# PGTN022_euclidean_logic.net
KiCad netlist of a schematic drawn in EAGLE
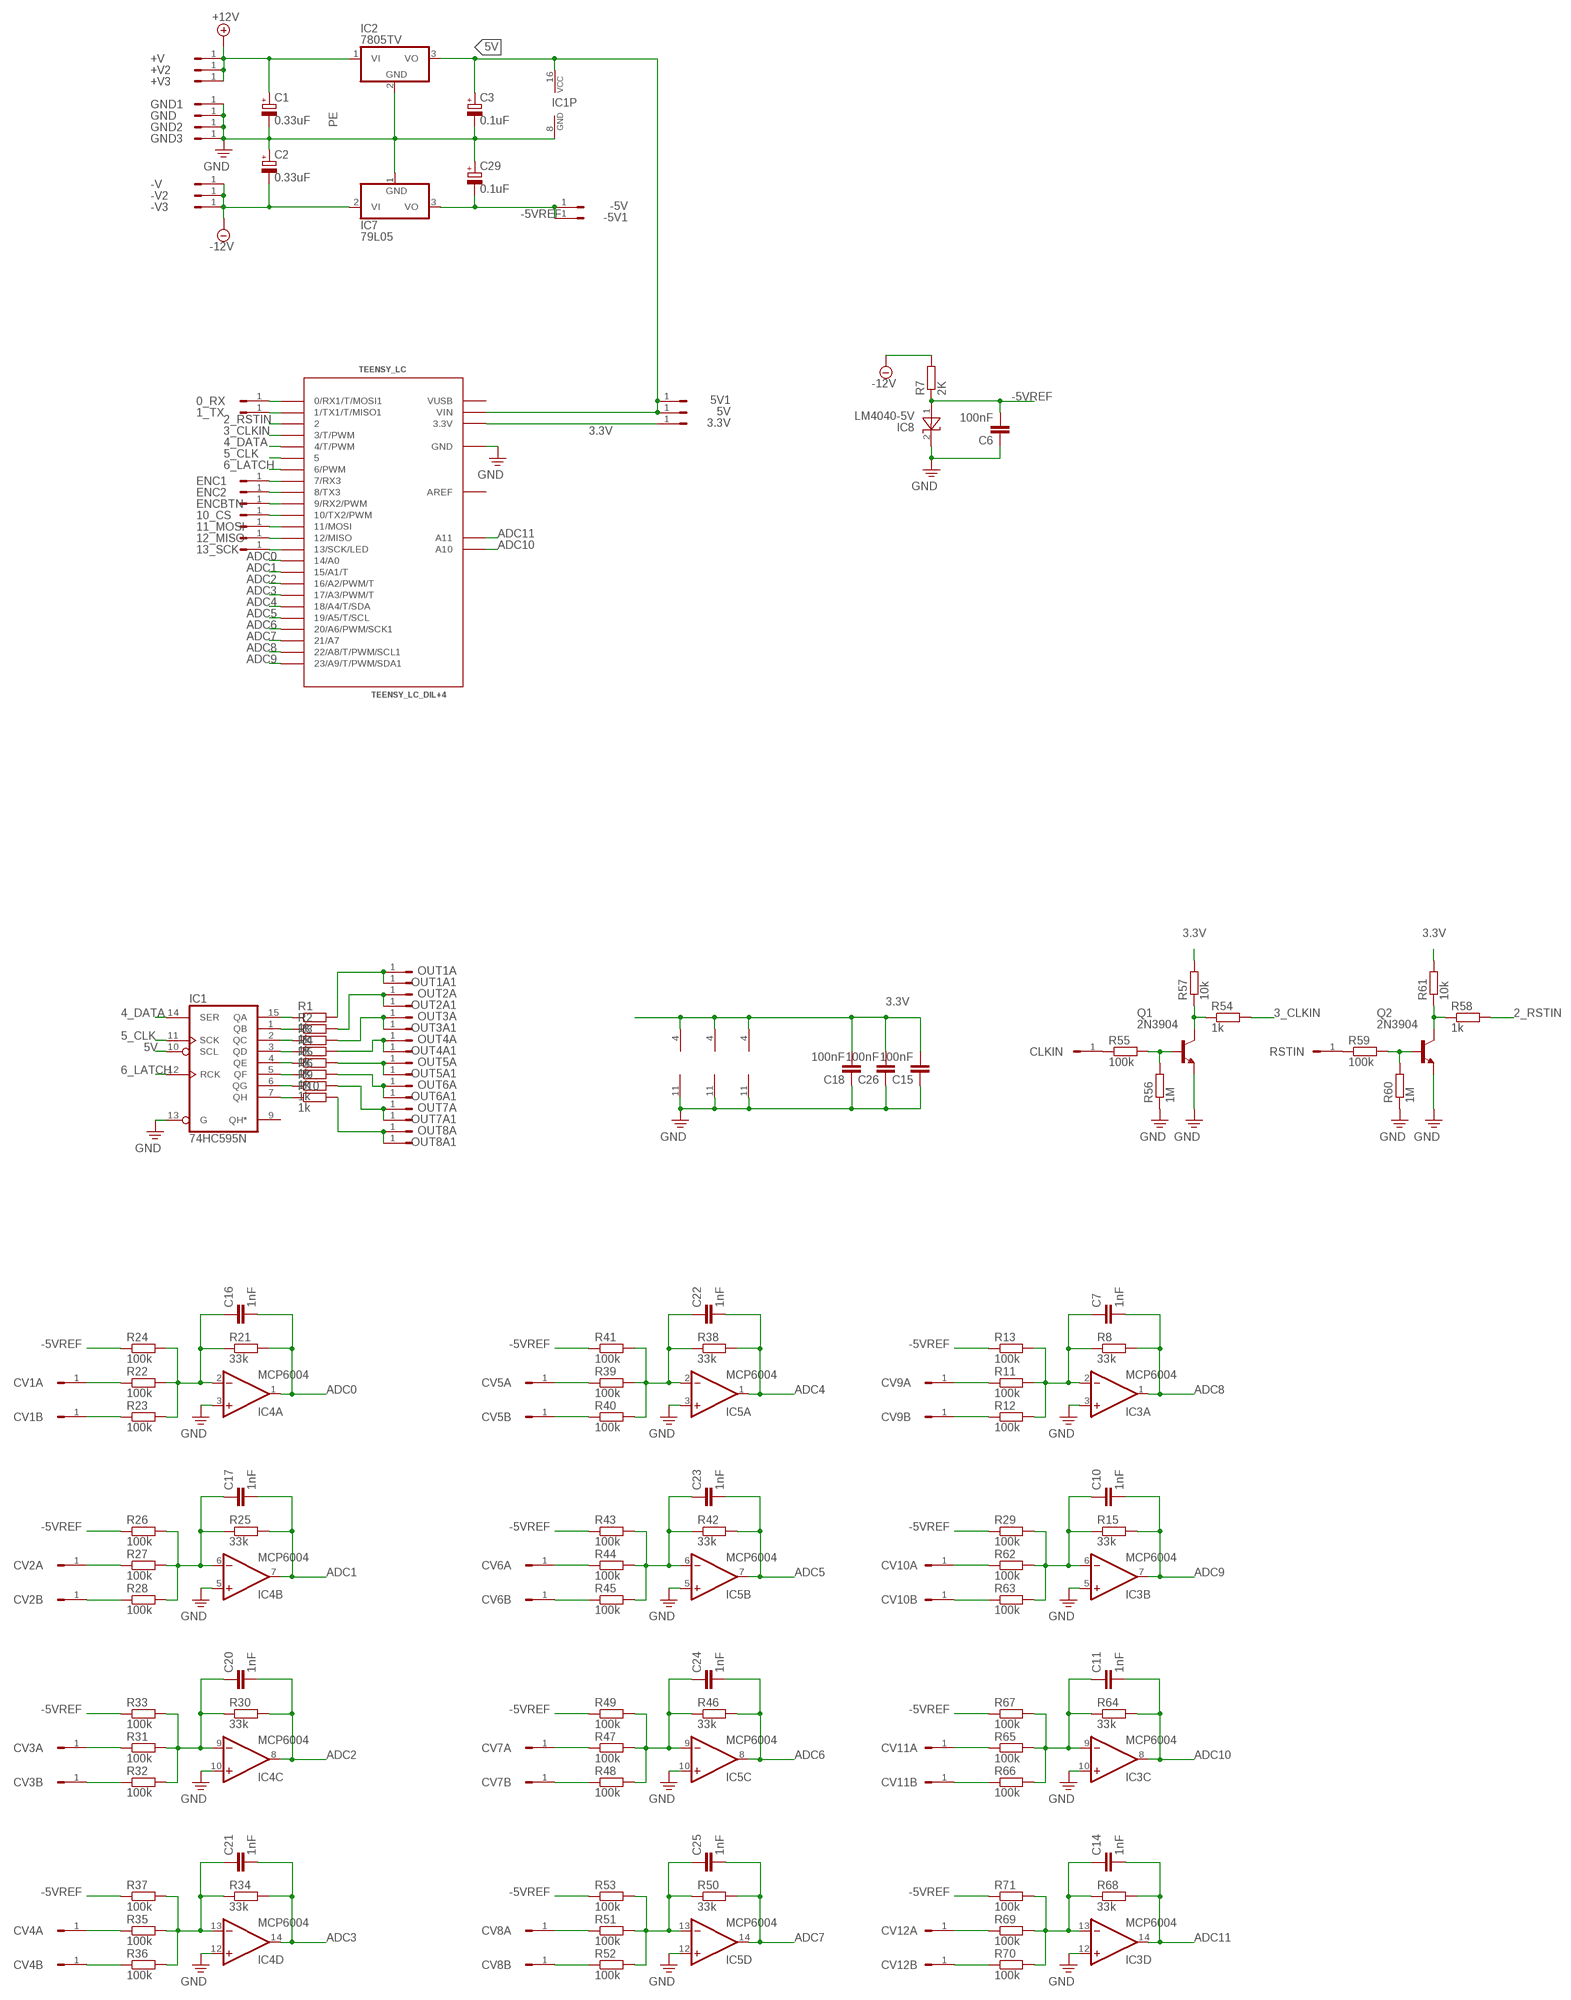
[diagram p0: schematic, sheet 1]

(export (version "E")
  (design (tool "Eeschema 10.0.6"))
  (components
    (comp (ref "+V")
      (value "HEADER/MALE/01")
      (footprint "eagle-import:HEADER_MALE_01")
      (fields (field (name "SPICEPREFIX") "X"))
      (libsource (lib "eagle-import") (part "HEADER/MALE/01"))
    )
    (comp (ref "+V2")
      (value "HEADER/MALE/01")
      (footprint "eagle-import:HEADER_MALE_01")
      (fields (field (name "SPICEPREFIX") "X"))
      (libsource (lib "eagle-import") (part "HEADER/MALE/01"))
    )
    (comp (ref "+V3")
      (value "HEADER/MALE/01")
      (footprint "eagle-import:HEADER_MALE_01")
      (fields (field (name "SPICEPREFIX") "X"))
      (libsource (lib "eagle-import") (part "HEADER/MALE/01"))
    )
    (comp (ref "-5V")
      (value "HEADER/MALE/01")
      (footprint "eagle-import:HEADER_MALE_01")
      (fields (field (name "SPICEPREFIX") "X"))
      (libsource (lib "eagle-import") (part "HEADER/MALE/01"))
    )
    (comp (ref "-5V1")
      (value "HEADER/MALE/01")
      (footprint "eagle-import:HEADER_MALE_01")
      (fields (field (name "SPICEPREFIX") "X"))
      (libsource (lib "eagle-import") (part "HEADER/MALE/01"))
    )
    (comp (ref "-V")
      (value "HEADER/MALE/01")
      (footprint "eagle-import:HEADER_MALE_01")
      (fields (field (name "SPICEPREFIX") "X"))
      (libsource (lib "eagle-import") (part "HEADER/MALE/01"))
    )
    (comp (ref "-V2")
      (value "HEADER/MALE/01")
      (footprint "eagle-import:HEADER_MALE_01")
      (fields (field (name "SPICEPREFIX") "X"))
      (libsource (lib "eagle-import") (part "HEADER/MALE/01"))
    )
    (comp (ref "-V3")
      (value "HEADER/MALE/01")
      (footprint "eagle-import:HEADER_MALE_01")
      (fields (field (name "SPICEPREFIX") "X"))
      (libsource (lib "eagle-import") (part "HEADER/MALE/01"))
    )
    (comp (ref "0_RX")
      (value "HEADER/MALE/01")
      (footprint "eagle-import:HEADER_MALE_01")
      (fields (field (name "SPICEPREFIX") "X"))
      (libsource (lib "eagle-import") (part "HEADER/MALE/01"))
    )
    (comp (ref "1_TX")
      (value "HEADER/MALE/01")
      (footprint "eagle-import:HEADER_MALE_01")
      (fields (field (name "SPICEPREFIX") "X"))
      (libsource (lib "eagle-import") (part "HEADER/MALE/01"))
    )
    (comp (ref "3.3V")
      (value "HEADER/MALE/01")
      (footprint "eagle-import:HEADER_MALE_01")
      (fields (field (name "SPICEPREFIX") "X"))
      (libsource (lib "eagle-import") (part "HEADER/MALE/01"))
    )
    (comp (ref "5V")
      (value "HEADER/MALE/01")
      (footprint "eagle-import:HEADER_MALE_01")
      (fields (field (name "SPICEPREFIX") "X"))
      (libsource (lib "eagle-import") (part "HEADER/MALE/01"))
    )
    (comp (ref "5V1")
      (value "HEADER/MALE/01")
      (footprint "eagle-import:HEADER_MALE_01")
      (fields (field (name "SPICEPREFIX") "X"))
      (libsource (lib "eagle-import") (part "HEADER/MALE/01"))
    )
    (comp (ref "10_CS")
      (value "HEADER/MALE/01")
      (footprint "eagle-import:HEADER_MALE_01")
      (fields (field (name "SPICEPREFIX") "X"))
      (libsource (lib "eagle-import") (part "HEADER/MALE/01"))
    )
    (comp (ref "11_MOSI")
      (value "HEADER/MALE/01")
      (footprint "eagle-import:HEADER_MALE_01")
      (fields (field (name "SPICEPREFIX") "X"))
      (libsource (lib "eagle-import") (part "HEADER/MALE/01"))
    )
    (comp (ref "12_MISO")
      (value "HEADER/MALE/01")
      (footprint "eagle-import:HEADER_MALE_01")
      (fields (field (name "SPICEPREFIX") "X"))
      (libsource (lib "eagle-import") (part "HEADER/MALE/01"))
    )
    (comp (ref "13_SCK")
      (value "HEADER/MALE/01")
      (footprint "eagle-import:HEADER_MALE_01")
      (fields (field (name "SPICEPREFIX") "X"))
      (libsource (lib "eagle-import") (part "HEADER/MALE/01"))
    )
    (comp (ref "C1")
      (value "0.33uF")
      (footprint "eagle-import:E2,5-6")
      (fields (field (name "SPICEPREFIX") "C"))
      (libsource (lib "eagle-import") (part "CAPACITOR/POLARIZEDE2.5-6"))
    )
    (comp (ref "C2")
      (value "0.33uF")
      (footprint "eagle-import:E2,5-6")
      (fields (field (name "SPICEPREFIX") "C"))
      (libsource (lib "eagle-import") (part "CAPACITOR/POLARIZEDE2.5-6"))
    )
    (comp (ref "C3")
      (value "0.1uF")
      (footprint "eagle-import:E2,5-6")
      (fields (field (name "SPICEPREFIX") "C"))
      (libsource (lib "eagle-import") (part "CAPACITOR/POLARIZEDE2.5-6"))
    )
    (comp (ref "C6")
      (value "100nF")
      (footprint "eagle-import:CERAMICDISC_5")
      (libsource (lib "eagle-import") (part "CAPACITORCERAMICDISC/5"))
    )
    (comp (ref "C7")
      (value "1nF")
      (footprint "eagle-import:CERAMICDISC_5")
      (libsource (lib "eagle-import") (part "CAPACITORCERAMICDISC/5"))
    )
    (comp (ref "C10")
      (value "1nF")
      (footprint "eagle-import:CERAMICDISC_5")
      (libsource (lib "eagle-import") (part "CAPACITORCERAMICDISC/5"))
    )
    (comp (ref "C11")
      (value "1nF")
      (footprint "eagle-import:CERAMICDISC_5")
      (libsource (lib "eagle-import") (part "CAPACITORCERAMICDISC/5"))
    )
    (comp (ref "C14")
      (value "1nF")
      (footprint "eagle-import:CERAMICDISC_5")
      (libsource (lib "eagle-import") (part "CAPACITORCERAMICDISC/5"))
    )
    (comp (ref "C15")
      (value "100nF")
      (footprint "eagle-import:CERAMICDISC_5")
      (libsource (lib "eagle-import") (part "CAPACITORCERAMICDISC/5"))
    )
    (comp (ref "C16")
      (value "1nF")
      (footprint "eagle-import:CERAMICDISC_5")
      (libsource (lib "eagle-import") (part "CAPACITORCERAMICDISC/5"))
    )
    (comp (ref "C17")
      (value "1nF")
      (footprint "eagle-import:CERAMICDISC_5")
      (libsource (lib "eagle-import") (part "CAPACITORCERAMICDISC/5"))
    )
    (comp (ref "C18")
      (value "100nF")
      (footprint "eagle-import:CERAMICDISC_5")
      (libsource (lib "eagle-import") (part "CAPACITORCERAMICDISC/5"))
    )
    (comp (ref "C20")
      (value "1nF")
      (footprint "eagle-import:CERAMICDISC_5")
      (libsource (lib "eagle-import") (part "CAPACITORCERAMICDISC/5"))
    )
    (comp (ref "C21")
      (value "1nF")
      (footprint "eagle-import:CERAMICDISC_5")
      (libsource (lib "eagle-import") (part "CAPACITORCERAMICDISC/5"))
    )
    (comp (ref "C22")
      (value "1nF")
      (footprint "eagle-import:CERAMICDISC_5")
      (libsource (lib "eagle-import") (part "CAPACITORCERAMICDISC/5"))
    )
    (comp (ref "C23")
      (value "1nF")
      (footprint "eagle-import:CERAMICDISC_5")
      (libsource (lib "eagle-import") (part "CAPACITORCERAMICDISC/5"))
    )
    (comp (ref "C24")
      (value "1nF")
      (footprint "eagle-import:CERAMICDISC_5")
      (libsource (lib "eagle-import") (part "CAPACITORCERAMICDISC/5"))
    )
    (comp (ref "C25")
      (value "1nF")
      (footprint "eagle-import:CERAMICDISC_5")
      (libsource (lib "eagle-import") (part "CAPACITORCERAMICDISC/5"))
    )
    (comp (ref "C26")
      (value "100nF")
      (footprint "eagle-import:CERAMICDISC_5")
      (libsource (lib "eagle-import") (part "CAPACITORCERAMICDISC/5"))
    )
    (comp (ref "C29")
      (value "0.1uF")
      (footprint "eagle-import:E2,5-6")
      (fields (field (name "SPICEPREFIX") "C"))
      (libsource (lib "eagle-import") (part "CAPACITOR/POLARIZEDE2.5-6"))
    )
    (comp (ref "CLKIN")
      (value "HEADER/MALE/01")
      (footprint "eagle-import:HEADER_MALE_01")
      (fields (field (name "SPICEPREFIX") "X"))
      (libsource (lib "eagle-import") (part "HEADER/MALE/01"))
    )
    (comp (ref "CV1A")
      (value "HEADER/MALE/01")
      (footprint "eagle-import:HEADER_MALE_01")
      (fields (field (name "SPICEPREFIX") "X"))
      (libsource (lib "eagle-import") (part "HEADER/MALE/01"))
    )
    (comp (ref "CV1B")
      (value "HEADER/MALE/01")
      (footprint "eagle-import:HEADER_MALE_01")
      (fields (field (name "SPICEPREFIX") "X"))
      (libsource (lib "eagle-import") (part "HEADER/MALE/01"))
    )
    (comp (ref "CV2A")
      (value "HEADER/MALE/01")
      (footprint "eagle-import:HEADER_MALE_01")
      (fields (field (name "SPICEPREFIX") "X"))
      (libsource (lib "eagle-import") (part "HEADER/MALE/01"))
    )
    (comp (ref "CV2B")
      (value "HEADER/MALE/01")
      (footprint "eagle-import:HEADER_MALE_01")
      (fields (field (name "SPICEPREFIX") "X"))
      (libsource (lib "eagle-import") (part "HEADER/MALE/01"))
    )
    (comp (ref "CV3A")
      (value "HEADER/MALE/01")
      (footprint "eagle-import:HEADER_MALE_01")
      (fields (field (name "SPICEPREFIX") "X"))
      (libsource (lib "eagle-import") (part "HEADER/MALE/01"))
    )
    (comp (ref "CV3B")
      (value "HEADER/MALE/01")
      (footprint "eagle-import:HEADER_MALE_01")
      (fields (field (name "SPICEPREFIX") "X"))
      (libsource (lib "eagle-import") (part "HEADER/MALE/01"))
    )
    (comp (ref "CV4A")
      (value "HEADER/MALE/01")
      (footprint "eagle-import:HEADER_MALE_01")
      (fields (field (name "SPICEPREFIX") "X"))
      (libsource (lib "eagle-import") (part "HEADER/MALE/01"))
    )
    (comp (ref "CV4B")
      (value "HEADER/MALE/01")
      (footprint "eagle-import:HEADER_MALE_01")
      (fields (field (name "SPICEPREFIX") "X"))
      (libsource (lib "eagle-import") (part "HEADER/MALE/01"))
    )
    (comp (ref "CV5A")
      (value "HEADER/MALE/01")
      (footprint "eagle-import:HEADER_MALE_01")
      (fields (field (name "SPICEPREFIX") "X"))
      (libsource (lib "eagle-import") (part "HEADER/MALE/01"))
    )
    (comp (ref "CV5B")
      (value "HEADER/MALE/01")
      (footprint "eagle-import:HEADER_MALE_01")
      (fields (field (name "SPICEPREFIX") "X"))
      (libsource (lib "eagle-import") (part "HEADER/MALE/01"))
    )
    (comp (ref "CV6A")
      (value "HEADER/MALE/01")
      (footprint "eagle-import:HEADER_MALE_01")
      (fields (field (name "SPICEPREFIX") "X"))
      (libsource (lib "eagle-import") (part "HEADER/MALE/01"))
    )
    (comp (ref "CV6B")
      (value "HEADER/MALE/01")
      (footprint "eagle-import:HEADER_MALE_01")
      (fields (field (name "SPICEPREFIX") "X"))
      (libsource (lib "eagle-import") (part "HEADER/MALE/01"))
    )
    (comp (ref "CV7A")
      (value "HEADER/MALE/01")
      (footprint "eagle-import:HEADER_MALE_01")
      (fields (field (name "SPICEPREFIX") "X"))
      (libsource (lib "eagle-import") (part "HEADER/MALE/01"))
    )
    (comp (ref "CV7B")
      (value "HEADER/MALE/01")
      (footprint "eagle-import:HEADER_MALE_01")
      (fields (field (name "SPICEPREFIX") "X"))
      (libsource (lib "eagle-import") (part "HEADER/MALE/01"))
    )
    (comp (ref "CV8A")
      (value "HEADER/MALE/01")
      (footprint "eagle-import:HEADER_MALE_01")
      (fields (field (name "SPICEPREFIX") "X"))
      (libsource (lib "eagle-import") (part "HEADER/MALE/01"))
    )
    (comp (ref "CV8B")
      (value "HEADER/MALE/01")
      (footprint "eagle-import:HEADER_MALE_01")
      (fields (field (name "SPICEPREFIX") "X"))
      (libsource (lib "eagle-import") (part "HEADER/MALE/01"))
    )
    (comp (ref "CV9A")
      (value "HEADER/MALE/01")
      (footprint "eagle-import:HEADER_MALE_01")
      (fields (field (name "SPICEPREFIX") "X"))
      (libsource (lib "eagle-import") (part "HEADER/MALE/01"))
    )
    (comp (ref "CV9B")
      (value "HEADER/MALE/01")
      (footprint "eagle-import:HEADER_MALE_01")
      (fields (field (name "SPICEPREFIX") "X"))
      (libsource (lib "eagle-import") (part "HEADER/MALE/01"))
    )
    (comp (ref "CV10A")
      (value "HEADER/MALE/01")
      (footprint "eagle-import:HEADER_MALE_01")
      (fields (field (name "SPICEPREFIX") "X"))
      (libsource (lib "eagle-import") (part "HEADER/MALE/01"))
    )
    (comp (ref "CV10B")
      (value "HEADER/MALE/01")
      (footprint "eagle-import:HEADER_MALE_01")
      (fields (field (name "SPICEPREFIX") "X"))
      (libsource (lib "eagle-import") (part "HEADER/MALE/01"))
    )
    (comp (ref "CV11A")
      (value "HEADER/MALE/01")
      (footprint "eagle-import:HEADER_MALE_01")
      (fields (field (name "SPICEPREFIX") "X"))
      (libsource (lib "eagle-import") (part "HEADER/MALE/01"))
    )
    (comp (ref "CV11B")
      (value "HEADER/MALE/01")
      (footprint "eagle-import:HEADER_MALE_01")
      (fields (field (name "SPICEPREFIX") "X"))
      (libsource (lib "eagle-import") (part "HEADER/MALE/01"))
    )
    (comp (ref "CV12A")
      (value "HEADER/MALE/01")
      (footprint "eagle-import:HEADER_MALE_01")
      (fields (field (name "SPICEPREFIX") "X"))
      (libsource (lib "eagle-import") (part "HEADER/MALE/01"))
    )
    (comp (ref "CV12B")
      (value "HEADER/MALE/01")
      (footprint "eagle-import:HEADER_MALE_01")
      (fields (field (name "SPICEPREFIX") "X"))
      (libsource (lib "eagle-import") (part "HEADER/MALE/01"))
    )
    (comp (ref "ENC1")
      (value "HEADER/MALE/01")
      (footprint "eagle-import:HEADER_MALE_01")
      (fields (field (name "SPICEPREFIX") "X"))
      (libsource (lib "eagle-import") (part "HEADER/MALE/01"))
    )
    (comp (ref "ENC2")
      (value "HEADER/MALE/01")
      (footprint "eagle-import:HEADER_MALE_01")
      (fields (field (name "SPICEPREFIX") "X"))
      (libsource (lib "eagle-import") (part "HEADER/MALE/01"))
    )
    (comp (ref "ENCBTN")
      (value "HEADER/MALE/01")
      (footprint "eagle-import:HEADER_MALE_01")
      (fields (field (name "SPICEPREFIX") "X"))
      (libsource (lib "eagle-import") (part "HEADER/MALE/01"))
    )
    (comp (ref "GND")
      (value "HEADER/MALE/01")
      (footprint "eagle-import:HEADER_MALE_01")
      (fields (field (name "SPICEPREFIX") "X"))
      (libsource (lib "eagle-import") (part "HEADER/MALE/01"))
    )
    (comp (ref "GND1")
      (value "HEADER/MALE/01")
      (footprint "eagle-import:HEADER_MALE_01")
      (fields (field (name "SPICEPREFIX") "X"))
      (libsource (lib "eagle-import") (part "HEADER/MALE/01"))
    )
    (comp (ref "GND2")
      (value "HEADER/MALE/01")
      (footprint "eagle-import:HEADER_MALE_01")
      (fields (field (name "SPICEPREFIX") "X"))
      (libsource (lib "eagle-import") (part "HEADER/MALE/01"))
    )
    (comp (ref "GND3")
      (value "HEADER/MALE/01")
      (footprint "eagle-import:HEADER_MALE_01")
      (fields (field (name "SPICEPREFIX") "X"))
      (libsource (lib "eagle-import") (part "HEADER/MALE/01"))
    )
    (comp (ref "IC1")
      (value "74HC595N")
      (footprint "eagle-import:DIL16")
      (libsource (lib "eagle-import") (part "74595NHC"))
    )
    (comp (ref "IC2")
      (value "7805TV")
      (footprint "eagle-import:TO220V")
      (libsource (lib "eagle-import") (part "78TV05"))
    )
    (comp (ref "IC3")
      (value "MCP6004")
      (footprint "eagle-import:DIL14")
      (libsource (lib "eagle-import") (part "TL074P"))
    )
    (comp (ref "IC4")
      (value "MCP6004")
      (footprint "eagle-import:DIL14")
      (libsource (lib "eagle-import") (part "TL074P"))
    )
    (comp (ref "IC5")
      (value "MCP6004")
      (footprint "eagle-import:DIL14")
      (libsource (lib "eagle-import") (part "TL074P"))
    )
    (comp (ref "IC7")
      (value "79L05")
      (footprint "eagle-import:TO92")
      (libsource (lib "eagle-import") (part "79ZL05"))
    )
    (comp (ref "IC8")
      (value "LM4040-5V")
      (footprint "eagle-import:TO92")
      (libsource (lib "eagle-import") (part "LM4040"))
    )
    (comp (ref "OUT1A")
      (value "HEADER/MALE/01")
      (footprint "eagle-import:HEADER_MALE_01")
      (fields (field (name "SPICEPREFIX") "X"))
      (libsource (lib "eagle-import") (part "HEADER/MALE/01"))
    )
    (comp (ref "OUT1A1")
      (value "HEADER/MALE/01")
      (footprint "eagle-import:HEADER_MALE_01")
      (fields (field (name "SPICEPREFIX") "X"))
      (libsource (lib "eagle-import") (part "HEADER/MALE/01"))
    )
    (comp (ref "OUT2A")
      (value "HEADER/MALE/01")
      (footprint "eagle-import:HEADER_MALE_01")
      (fields (field (name "SPICEPREFIX") "X"))
      (libsource (lib "eagle-import") (part "HEADER/MALE/01"))
    )
    (comp (ref "OUT2A1")
      (value "HEADER/MALE/01")
      (footprint "eagle-import:HEADER_MALE_01")
      (fields (field (name "SPICEPREFIX") "X"))
      (libsource (lib "eagle-import") (part "HEADER/MALE/01"))
    )
    (comp (ref "OUT3A")
      (value "HEADER/MALE/01")
      (footprint "eagle-import:HEADER_MALE_01")
      (fields (field (name "SPICEPREFIX") "X"))
      (libsource (lib "eagle-import") (part "HEADER/MALE/01"))
    )
    (comp (ref "OUT3A1")
      (value "HEADER/MALE/01")
      (footprint "eagle-import:HEADER_MALE_01")
      (fields (field (name "SPICEPREFIX") "X"))
      (libsource (lib "eagle-import") (part "HEADER/MALE/01"))
    )
    (comp (ref "OUT4A")
      (value "HEADER/MALE/01")
      (footprint "eagle-import:HEADER_MALE_01")
      (fields (field (name "SPICEPREFIX") "X"))
      (libsource (lib "eagle-import") (part "HEADER/MALE/01"))
    )
    (comp (ref "OUT4A1")
      (value "HEADER/MALE/01")
      (footprint "eagle-import:HEADER_MALE_01")
      (fields (field (name "SPICEPREFIX") "X"))
      (libsource (lib "eagle-import") (part "HEADER/MALE/01"))
    )
    (comp (ref "OUT5A")
      (value "HEADER/MALE/01")
      (footprint "eagle-import:HEADER_MALE_01")
      (fields (field (name "SPICEPREFIX") "X"))
      (libsource (lib "eagle-import") (part "HEADER/MALE/01"))
    )
    (comp (ref "OUT5A1")
      (value "HEADER/MALE/01")
      (footprint "eagle-import:HEADER_MALE_01")
      (fields (field (name "SPICEPREFIX") "X"))
      (libsource (lib "eagle-import") (part "HEADER/MALE/01"))
    )
    (comp (ref "OUT6A")
      (value "HEADER/MALE/01")
      (footprint "eagle-import:HEADER_MALE_01")
      (fields (field (name "SPICEPREFIX") "X"))
      (libsource (lib "eagle-import") (part "HEADER/MALE/01"))
    )
    (comp (ref "OUT6A1")
      (value "HEADER/MALE/01")
      (footprint "eagle-import:HEADER_MALE_01")
      (fields (field (name "SPICEPREFIX") "X"))
      (libsource (lib "eagle-import") (part "HEADER/MALE/01"))
    )
    (comp (ref "OUT7A")
      (value "HEADER/MALE/01")
      (footprint "eagle-import:HEADER_MALE_01")
      (fields (field (name "SPICEPREFIX") "X"))
      (libsource (lib "eagle-import") (part "HEADER/MALE/01"))
    )
    (comp (ref "OUT7A1")
      (value "HEADER/MALE/01")
      (footprint "eagle-import:HEADER_MALE_01")
      (fields (field (name "SPICEPREFIX") "X"))
      (libsource (lib "eagle-import") (part "HEADER/MALE/01"))
    )
    (comp (ref "OUT8A")
      (value "HEADER/MALE/01")
      (footprint "eagle-import:HEADER_MALE_01")
      (fields (field (name "SPICEPREFIX") "X"))
      (libsource (lib "eagle-import") (part "HEADER/MALE/01"))
    )
    (comp (ref "OUT8A1")
      (value "HEADER/MALE/01")
      (footprint "eagle-import:HEADER_MALE_01")
      (fields (field (name "SPICEPREFIX") "X"))
      (libsource (lib "eagle-import") (part "HEADER/MALE/01"))
    )
    (comp (ref "Q1")
      (value "2N3904")
      (footprint "eagle-import:TO92")
      (libsource (lib "eagle-import") (part "2N3904"))
    )
    (comp (ref "Q2")
      (value "2N3904")
      (footprint "eagle-import:TO92")
      (libsource (lib "eagle-import") (part "2N3904"))
    )
    (comp (ref "R1")
      (value "1k")
      (footprint "eagle-import:RESISTOR_7.5")
      (libsource (lib "eagle-import") (part "RESISTORRESISTOR/UPRIGHT/7.5"))
    )
    (comp (ref "R2")
      (value "1k")
      (footprint "eagle-import:RESISTOR_7.5")
      (libsource (lib "eagle-import") (part "RESISTORRESISTOR/UPRIGHT/7.5"))
    )
    (comp (ref "R3")
      (value "1k")
      (footprint "eagle-import:RESISTOR_7.5")
      (libsource (lib "eagle-import") (part "RESISTORRESISTOR/UPRIGHT/7.5"))
    )
    (comp (ref "R4")
      (value "1k")
      (footprint "eagle-import:RESISTOR_7.5")
      (libsource (lib "eagle-import") (part "RESISTORRESISTOR/UPRIGHT/7.5"))
    )
    (comp (ref "R5")
      (value "1k")
      (footprint "eagle-import:RESISTOR_7.5")
      (libsource (lib "eagle-import") (part "RESISTORRESISTOR/UPRIGHT/7.5"))
    )
    (comp (ref "R6")
      (value "1k")
      (footprint "eagle-import:RESISTOR_7.5")
      (libsource (lib "eagle-import") (part "RESISTORRESISTOR/UPRIGHT/7.5"))
    )
    (comp (ref "R7")
      (value "2K")
      (footprint "eagle-import:RESISTOR_7.5")
      (libsource (lib "eagle-import") (part "RESISTORRESISTOR/UPRIGHT/7.5"))
    )
    (comp (ref "R8")
      (value "33k")
      (footprint "eagle-import:RESISTOR_7.5")
      (libsource (lib "eagle-import") (part "RESISTORRESISTOR/UPRIGHT/7.5"))
    )
    (comp (ref "R9")
      (value "1k")
      (footprint "eagle-import:RESISTOR_7.5")
      (libsource (lib "eagle-import") (part "RESISTORRESISTOR/UPRIGHT/7.5"))
    )
    (comp (ref "R10")
      (value "1k")
      (footprint "eagle-import:RESISTOR_7.5")
      (libsource (lib "eagle-import") (part "RESISTORRESISTOR/UPRIGHT/7.5"))
    )
    (comp (ref "R11")
      (value "100k")
      (footprint "eagle-import:RESISTOR_7.5")
      (libsource (lib "eagle-import") (part "RESISTORRESISTOR/UPRIGHT/7.5"))
    )
    (comp (ref "R12")
      (value "100k")
      (footprint "eagle-import:RESISTOR_7.5")
      (libsource (lib "eagle-import") (part "RESISTORRESISTOR/UPRIGHT/7.5"))
    )
    (comp (ref "R13")
      (value "100k")
      (footprint "eagle-import:RESISTOR_7.5")
      (libsource (lib "eagle-import") (part "RESISTORRESISTOR/UPRIGHT/7.5"))
    )
    (comp (ref "R15")
      (value "33k")
      (footprint "eagle-import:RESISTOR_7.5")
      (libsource (lib "eagle-import") (part "RESISTORRESISTOR/UPRIGHT/7.5"))
    )
    (comp (ref "R21")
      (value "33k")
      (footprint "eagle-import:RESISTOR_7.5")
      (libsource (lib "eagle-import") (part "RESISTORRESISTOR/UPRIGHT/7.5"))
    )
    (comp (ref "R22")
      (value "100k")
      (footprint "eagle-import:RESISTOR_7.5")
      (libsource (lib "eagle-import") (part "RESISTORRESISTOR/UPRIGHT/7.5"))
    )
    (comp (ref "R23")
      (value "100k")
      (footprint "eagle-import:RESISTOR_7.5")
      (libsource (lib "eagle-import") (part "RESISTORRESISTOR/UPRIGHT/7.5"))
    )
    (comp (ref "R24")
      (value "100k")
      (footprint "eagle-import:RESISTOR_7.5")
      (libsource (lib "eagle-import") (part "RESISTORRESISTOR/UPRIGHT/7.5"))
    )
    (comp (ref "R25")
      (value "33k")
      (footprint "eagle-import:RESISTOR_7.5")
      (libsource (lib "eagle-import") (part "RESISTORRESISTOR/UPRIGHT/7.5"))
    )
    (comp (ref "R26")
      (value "100k")
      (footprint "eagle-import:RESISTOR_7.5")
      (libsource (lib "eagle-import") (part "RESISTORRESISTOR/UPRIGHT/7.5"))
    )
    (comp (ref "R27")
      (value "100k")
      (footprint "eagle-import:RESISTOR_7.5")
      (libsource (lib "eagle-import") (part "RESISTORRESISTOR/UPRIGHT/7.5"))
    )
    (comp (ref "R28")
      (value "100k")
      (footprint "eagle-import:RESISTOR_7.5")
      (libsource (lib "eagle-import") (part "RESISTORRESISTOR/UPRIGHT/7.5"))
    )
    (comp (ref "R29")
      (value "100k")
      (footprint "eagle-import:RESISTOR_7.5")
      (libsource (lib "eagle-import") (part "RESISTORRESISTOR/UPRIGHT/7.5"))
    )
    (comp (ref "R30")
      (value "33k")
      (footprint "eagle-import:RESISTOR_7.5")
      (libsource (lib "eagle-import") (part "RESISTORRESISTOR/UPRIGHT/7.5"))
    )
    (comp (ref "R31")
      (value "100k")
      (footprint "eagle-import:RESISTOR_7.5")
      (libsource (lib "eagle-import") (part "RESISTORRESISTOR/UPRIGHT/7.5"))
    )
    (comp (ref "R32")
      (value "100k")
      (footprint "eagle-import:RESISTOR_7.5")
      (libsource (lib "eagle-import") (part "RESISTORRESISTOR/UPRIGHT/7.5"))
    )
    (comp (ref "R33")
      (value "100k")
      (footprint "eagle-import:RESISTOR_7.5")
      (libsource (lib "eagle-import") (part "RESISTORRESISTOR/UPRIGHT/7.5"))
    )
    (comp (ref "R34")
      (value "33k")
      (footprint "eagle-import:RESISTOR_7.5")
      (libsource (lib "eagle-import") (part "RESISTORRESISTOR/UPRIGHT/7.5"))
    )
    (comp (ref "R35")
      (value "100k")
      (footprint "eagle-import:RESISTOR_7.5")
      (libsource (lib "eagle-import") (part "RESISTORRESISTOR/UPRIGHT/7.5"))
    )
    (comp (ref "R36")
      (value "100k")
      (footprint "eagle-import:RESISTOR_7.5")
      (libsource (lib "eagle-import") (part "RESISTORRESISTOR/UPRIGHT/7.5"))
    )
    (comp (ref "R37")
      (value "100k")
      (footprint "eagle-import:RESISTOR_7.5")
      (libsource (lib "eagle-import") (part "RESISTORRESISTOR/UPRIGHT/7.5"))
    )
    (comp (ref "R38")
      (value "33k")
      (footprint "eagle-import:RESISTOR_7.5")
      (libsource (lib "eagle-import") (part "RESISTORRESISTOR/UPRIGHT/7.5"))
    )
    (comp (ref "R39")
      (value "100k")
      (footprint "eagle-import:RESISTOR_7.5")
      (libsource (lib "eagle-import") (part "RESISTORRESISTOR/UPRIGHT/7.5"))
    )
    (comp (ref "R40")
      (value "100k")
      (footprint "eagle-import:RESISTOR_7.5")
      (libsource (lib "eagle-import") (part "RESISTORRESISTOR/UPRIGHT/7.5"))
    )
    (comp (ref "R41")
      (value "100k")
      (footprint "eagle-import:RESISTOR_7.5")
      (libsource (lib "eagle-import") (part "RESISTORRESISTOR/UPRIGHT/7.5"))
    )
    (comp (ref "R42")
      (value "33k")
      (footprint "eagle-import:RESISTOR_7.5")
      (libsource (lib "eagle-import") (part "RESISTORRESISTOR/UPRIGHT/7.5"))
    )
    (comp (ref "R43")
      (value "100k")
      (footprint "eagle-import:RESISTOR_7.5")
      (libsource (lib "eagle-import") (part "RESISTORRESISTOR/UPRIGHT/7.5"))
    )
    (comp (ref "R44")
      (value "100k")
      (footprint "eagle-import:RESISTOR_7.5")
      (libsource (lib "eagle-import") (part "RESISTORRESISTOR/UPRIGHT/7.5"))
    )
    (comp (ref "R45")
      (value "100k")
      (footprint "eagle-import:RESISTOR_7.5")
      (libsource (lib "eagle-import") (part "RESISTORRESISTOR/UPRIGHT/7.5"))
    )
    (comp (ref "R46")
      (value "33k")
      (footprint "eagle-import:RESISTOR_7.5")
      (libsource (lib "eagle-import") (part "RESISTORRESISTOR/UPRIGHT/7.5"))
    )
    (comp (ref "R47")
      (value "100k")
      (footprint "eagle-import:RESISTOR_7.5")
      (libsource (lib "eagle-import") (part "RESISTORRESISTOR/UPRIGHT/7.5"))
    )
    (comp (ref "R48")
      (value "100k")
      (footprint "eagle-import:RESISTOR_7.5")
      (libsource (lib "eagle-import") (part "RESISTORRESISTOR/UPRIGHT/7.5"))
    )
    (comp (ref "R49")
      (value "100k")
      (footprint "eagle-import:RESISTOR_7.5")
      (libsource (lib "eagle-import") (part "RESISTORRESISTOR/UPRIGHT/7.5"))
    )
    (comp (ref "R50")
      (value "33k")
      (footprint "eagle-import:RESISTOR_7.5")
      (libsource (lib "eagle-import") (part "RESISTORRESISTOR/UPRIGHT/7.5"))
    )
    (comp (ref "R51")
      (value "100k")
      (footprint "eagle-import:RESISTOR_7.5")
      (libsource (lib "eagle-import") (part "RESISTORRESISTOR/UPRIGHT/7.5"))
    )
    (comp (ref "R52")
      (value "100k")
      (footprint "eagle-import:RESISTOR_7.5")
      (libsource (lib "eagle-import") (part "RESISTORRESISTOR/UPRIGHT/7.5"))
    )
    (comp (ref "R53")
      (value "100k")
      (footprint "eagle-import:RESISTOR_7.5")
      (libsource (lib "eagle-import") (part "RESISTORRESISTOR/UPRIGHT/7.5"))
    )
    (comp (ref "R54")
      (value "1k")
      (footprint "eagle-import:RESISTOR_7.5")
      (libsource (lib "eagle-import") (part "RESISTORRESISTOR/UPRIGHT/7.5"))
    )
    (comp (ref "R55")
      (value "100k")
      (footprint "eagle-import:RESISTOR_7.5")
      (libsource (lib "eagle-import") (part "RESISTORRESISTOR/UPRIGHT/7.5"))
    )
    (comp (ref "R56")
      (value "1M")
      (footprint "eagle-import:RESISTOR_7.5")
      (libsource (lib "eagle-import") (part "RESISTORRESISTOR/UPRIGHT/7.5"))
    )
    (comp (ref "R57")
      (value "10k")
      (footprint "eagle-import:RESISTOR_7.5")
      (libsource (lib "eagle-import") (part "RESISTORRESISTOR/UPRIGHT/7.5"))
    )
    (comp (ref "R58")
      (value "1k")
      (footprint "eagle-import:RESISTOR_7.5")
      (libsource (lib "eagle-import") (part "RESISTORRESISTOR/UPRIGHT/7.5"))
    )
    (comp (ref "R59")
      (value "100k")
      (footprint "eagle-import:RESISTOR_7.5")
      (libsource (lib "eagle-import") (part "RESISTORRESISTOR/UPRIGHT/7.5"))
    )
    (comp (ref "R60")
      (value "1M")
      (footprint "eagle-import:RESISTOR_7.5")
      (libsource (lib "eagle-import") (part "RESISTORRESISTOR/UPRIGHT/7.5"))
    )
    (comp (ref "R61")
      (value "10k")
      (footprint "eagle-import:RESISTOR_7.5")
      (libsource (lib "eagle-import") (part "RESISTORRESISTOR/UPRIGHT/7.5"))
    )
    (comp (ref "R62")
      (value "100k")
      (footprint "eagle-import:RESISTOR_7.5")
      (libsource (lib "eagle-import") (part "RESISTORRESISTOR/UPRIGHT/7.5"))
    )
    (comp (ref "R63")
      (value "100k")
      (footprint "eagle-import:RESISTOR_7.5")
      (libsource (lib "eagle-import") (part "RESISTORRESISTOR/UPRIGHT/7.5"))
    )
    (comp (ref "R64")
      (value "33k")
      (footprint "eagle-import:RESISTOR_7.5")
      (libsource (lib "eagle-import") (part "RESISTORRESISTOR/UPRIGHT/7.5"))
    )
    (comp (ref "R65")
      (value "100k")
      (footprint "eagle-import:RESISTOR_7.5")
      (libsource (lib "eagle-import") (part "RESISTORRESISTOR/UPRIGHT/7.5"))
    )
    (comp (ref "R66")
      (value "100k")
      (footprint "eagle-import:RESISTOR_7.5")
      (libsource (lib "eagle-import") (part "RESISTORRESISTOR/UPRIGHT/7.5"))
    )
    (comp (ref "R67")
      (value "100k")
      (footprint "eagle-import:RESISTOR_7.5")
      (libsource (lib "eagle-import") (part "RESISTORRESISTOR/UPRIGHT/7.5"))
    )
    (comp (ref "R68")
      (value "33k")
      (footprint "eagle-import:RESISTOR_7.5")
      (libsource (lib "eagle-import") (part "RESISTORRESISTOR/UPRIGHT/7.5"))
    )
    (comp (ref "R69")
      (value "100k")
      (footprint "eagle-import:RESISTOR_7.5")
      (libsource (lib "eagle-import") (part "RESISTORRESISTOR/UPRIGHT/7.5"))
    )
    (comp (ref "R70")
      (value "100k")
      (footprint "eagle-import:RESISTOR_7.5")
      (libsource (lib "eagle-import") (part "RESISTORRESISTOR/UPRIGHT/7.5"))
    )
    (comp (ref "R71")
      (value "100k")
      (footprint "eagle-import:RESISTOR_7.5")
      (libsource (lib "eagle-import") (part "RESISTORRESISTOR/UPRIGHT/7.5"))
    )
    (comp (ref "RSTIN")
      (value "HEADER/MALE/01")
      (footprint "eagle-import:HEADER_MALE_01")
      (fields (field (name "SPICEPREFIX") "X"))
      (libsource (lib "eagle-import") (part "HEADER/MALE/01"))
    )
    (comp (ref "TEENSY_LC")
      (value "TEENSY_LC_DIL+4")
      (footprint "eagle-import:TEENSY_3.0-3.2&LC_DIL+4")
      (libsource (lib "eagle-import") (part "TEENSY_LC_DIL+4"))
    )
  )
  (nets
    (net (code "1") (name "+12V") (class "Default")
      (node (ref "+V") (pin "1") (pinfunction "3_1") (pintype "passive"))
      (node (ref "+V2") (pin "1") (pinfunction "3_1") (pintype "passive"))
      (node (ref "+V3") (pin "1") (pinfunction "3_1") (pintype "passive"))
      (node (ref "C1") (pin "+") (pinfunction "+_+") (pintype "passive"))
      (node (ref "IC2") (pin "1") (pinfunction "VI_1") (pintype "input"))
    )
    (net (code "2") (name "-12V") (class "Default")
      (node (ref "-V") (pin "1") (pinfunction "3_1") (pintype "passive"))
      (node (ref "-V2") (pin "1") (pinfunction "3_1") (pintype "passive"))
      (node (ref "-V3") (pin "1") (pinfunction "3_1") (pintype "passive"))
      (node (ref "C2") (pin "-") (pinfunction "-_-") (pintype "passive"))
      (node (ref "IC7") (pin "2") (pinfunction "VI_2") (pintype "input"))
      (node (ref "R7") (pin "2") (pinfunction "2_2") (pintype "passive"))
    )
    (net (code "3") (name "/-5VREF") (class "Default")
      (node (ref "-5V") (pin "1") (pinfunction "3_1") (pintype "passive"))
      (node (ref "-5V1") (pin "1") (pinfunction "3_1") (pintype "passive"))
      (node (ref "C29") (pin "-") (pinfunction "-_-") (pintype "passive"))
      (node (ref "C6") (pin "2") (pinfunction "2_2") (pintype "passive"))
      (node (ref "IC7") (pin "3") (pinfunction "VO_3") (pintype "passive"))
      (node (ref "IC8") (pin "1") (pinfunction "A_1") (pintype "output"))
      (node (ref "R13") (pin "1") (pinfunction "1_1") (pintype "passive"))
      (node (ref "R24") (pin "1") (pinfunction "1_1") (pintype "passive"))
      (node (ref "R26") (pin "1") (pinfunction "1_1") (pintype "passive"))
      (node (ref "R29") (pin "1") (pinfunction "1_1") (pintype "passive"))
      (node (ref "R33") (pin "1") (pinfunction "1_1") (pintype "passive"))
      (node (ref "R37") (pin "1") (pinfunction "1_1") (pintype "passive"))
      (node (ref "R41") (pin "1") (pinfunction "1_1") (pintype "passive"))
      (node (ref "R43") (pin "1") (pinfunction "1_1") (pintype "passive"))
      (node (ref "R49") (pin "1") (pinfunction "1_1") (pintype "passive"))
      (node (ref "R53") (pin "1") (pinfunction "1_1") (pintype "passive"))
      (node (ref "R67") (pin "1") (pinfunction "1_1") (pintype "passive"))
      (node (ref "R7") (pin "1") (pinfunction "1_1") (pintype "passive"))
      (node (ref "R71") (pin "1") (pinfunction "1_1") (pintype "passive"))
    )
    (net (code "4") (name "/2_RSTIN") (class "Default")
      (node (ref "R58") (pin "2") (pinfunction "2_2") (pintype "passive"))
      (node (ref "TEENSY_LC") (pin "2") (pinfunction "2_2") (pintype "bidirectional"))
    )
    (net (code "5") (name "/3.3V") (class "Default")
      (node (ref "3.3V") (pin "1") (pinfunction "3_1") (pintype "passive"))
      (node (ref "C15") (pin "2") (pinfunction "2_2") (pintype "passive"))
      (node (ref "C18") (pin "2") (pinfunction "2_2") (pintype "passive"))
      (node (ref "C26") (pin "2") (pinfunction "2_2") (pintype "passive"))
      (node (ref "IC3") (pin "4") (pinfunction "V+_4") (pintype "power_in"))
      (node (ref "IC4") (pin "4") (pinfunction "V+_4") (pintype "power_in"))
      (node (ref "IC5") (pin "4") (pinfunction "V+_4") (pintype "power_in"))
      (node (ref "R57") (pin "2") (pinfunction "2_2") (pintype "passive"))
      (node (ref "R61") (pin "2") (pinfunction "2_2") (pintype "passive"))
      (node (ref "TEENSY_LC") (pin "3.3V") (pinfunction "3.3V_3.3V") (pintype "power_in"))
    )
    (net (code "6") (name "/3_CLKIN") (class "Default")
      (node (ref "R54") (pin "2") (pinfunction "2_2") (pintype "passive"))
      (node (ref "TEENSY_LC") (pin "3") (pinfunction "3/T/PWM_3") (pintype "bidirectional"))
    )
    (net (code "7") (name "/4_DATA") (class "Default")
      (node (ref "IC1") (pin "14") (pinfunction "SER_14") (pintype "input"))
      (node (ref "TEENSY_LC") (pin "4") (pinfunction "4/T/PWM_4") (pintype "bidirectional"))
    )
    (net (code "8") (name "/5_CLK") (class "Default")
      (node (ref "IC1") (pin "11") (pinfunction "SCK_11") (pintype "input"))
      (node (ref "TEENSY_LC") (pin "5") (pinfunction "5_5") (pintype "bidirectional"))
    )
    (net (code "9") (name "/6_LATCH") (class "Default")
      (node (ref "IC1") (pin "12") (pinfunction "RCK_12") (pintype "input"))
      (node (ref "TEENSY_LC") (pin "6") (pinfunction "6/PWM_6") (pintype "bidirectional"))
    )
    (net (code "10") (name "/ADC0") (class "Default")
      (node (ref "C16") (pin "2") (pinfunction "2_2") (pintype "passive"))
      (node (ref "IC4") (pin "1") (pinfunction "OUT_1") (pintype "output"))
      (node (ref "R21") (pin "2") (pinfunction "2_2") (pintype "passive"))
      (node (ref "TEENSY_LC") (pin "14/A0") (pinfunction "14/A0_14/A0") (pintype "bidirectional"))
    )
    (net (code "11") (name "/ADC1") (class "Default")
      (node (ref "C17") (pin "2") (pinfunction "2_2") (pintype "passive"))
      (node (ref "IC4") (pin "7") (pinfunction "OUT_7") (pintype "output"))
      (node (ref "R25") (pin "2") (pinfunction "2_2") (pintype "passive"))
      (node (ref "TEENSY_LC") (pin "15/A1") (pinfunction "15/A1/T_15/A1") (pintype "bidirectional"))
    )
    (net (code "12") (name "/ADC2") (class "Default")
      (node (ref "C20") (pin "2") (pinfunction "2_2") (pintype "passive"))
      (node (ref "IC4") (pin "8") (pinfunction "OUT_8") (pintype "output"))
      (node (ref "R30") (pin "2") (pinfunction "2_2") (pintype "passive"))
      (node (ref "TEENSY_LC") (pin "16/A2") (pinfunction "16/A2/PWM/T_16/A2") (pintype "bidirectional"))
    )
    (net (code "13") (name "/ADC3") (class "Default")
      (node (ref "C21") (pin "2") (pinfunction "2_2") (pintype "passive"))
      (node (ref "IC4") (pin "14") (pinfunction "OUT_14") (pintype "output"))
      (node (ref "R34") (pin "2") (pinfunction "2_2") (pintype "passive"))
      (node (ref "TEENSY_LC") (pin "17/A3") (pinfunction "17/A3/PWM/T_17/A3") (pintype "bidirectional"))
    )
    (net (code "14") (name "/ADC4") (class "Default")
      (node (ref "C22") (pin "2") (pinfunction "2_2") (pintype "passive"))
      (node (ref "IC5") (pin "1") (pinfunction "OUT_1") (pintype "output"))
      (node (ref "R38") (pin "2") (pinfunction "2_2") (pintype "passive"))
      (node (ref "TEENSY_LC") (pin "18/A4") (pinfunction "18/A4/T/SDA_18/A4") (pintype "bidirectional"))
    )
    (net (code "15") (name "/ADC5") (class "Default")
      (node (ref "C23") (pin "2") (pinfunction "2_2") (pintype "passive"))
      (node (ref "IC5") (pin "7") (pinfunction "OUT_7") (pintype "output"))
      (node (ref "R42") (pin "2") (pinfunction "2_2") (pintype "passive"))
      (node (ref "TEENSY_LC") (pin "19/A5") (pinfunction "19/A5/T/SCL_19/A5") (pintype "bidirectional"))
    )
    (net (code "16") (name "/ADC6") (class "Default")
      (node (ref "C24") (pin "2") (pinfunction "2_2") (pintype "passive"))
      (node (ref "IC5") (pin "8") (pinfunction "OUT_8") (pintype "output"))
      (node (ref "R46") (pin "2") (pinfunction "2_2") (pintype "passive"))
      (node (ref "TEENSY_LC") (pin "20/A6") (pinfunction "20/A6/PWM/SCK1_20/A6") (pintype "bidirectional"))
    )
    (net (code "17") (name "/ADC7") (class "Default")
      (node (ref "C25") (pin "2") (pinfunction "2_2") (pintype "passive"))
      (node (ref "IC5") (pin "14") (pinfunction "OUT_14") (pintype "output"))
      (node (ref "R50") (pin "2") (pinfunction "2_2") (pintype "passive"))
      (node (ref "TEENSY_LC") (pin "21/A7") (pinfunction "21/A7_21/A7") (pintype "bidirectional"))
    )
    (net (code "18") (name "/ADC8") (class "Default")
      (node (ref "C7") (pin "2") (pinfunction "2_2") (pintype "passive"))
      (node (ref "IC3") (pin "1") (pinfunction "OUT_1") (pintype "output"))
      (node (ref "R8") (pin "2") (pinfunction "2_2") (pintype "passive"))
      (node (ref "TEENSY_LC") (pin "22/A8") (pinfunction "22/A8/T/PWM/SCL1_22/A8") (pintype "bidirectional"))
    )
    (net (code "19") (name "/ADC9") (class "Default")
      (node (ref "C10") (pin "2") (pinfunction "2_2") (pintype "passive"))
      (node (ref "IC3") (pin "7") (pinfunction "OUT_7") (pintype "output"))
      (node (ref "R15") (pin "2") (pinfunction "2_2") (pintype "passive"))
      (node (ref "TEENSY_LC") (pin "23/A9") (pinfunction "23/A9/T/PWM/SDA1_23/A9") (pintype "bidirectional"))
    )
    (net (code "20") (name "/ADC10") (class "Default")
      (node (ref "C11") (pin "2") (pinfunction "2_2") (pintype "passive"))
      (node (ref "IC3") (pin "8") (pinfunction "OUT_8") (pintype "output"))
      (node (ref "R64") (pin "2") (pinfunction "2_2") (pintype "passive"))
      (node (ref "TEENSY_LC") (pin "A10") (pinfunction "A10_A10") (pintype "bidirectional"))
    )
    (net (code "21") (name "/ADC11") (class "Default")
      (node (ref "C14") (pin "2") (pinfunction "2_2") (pintype "passive"))
      (node (ref "IC3") (pin "14") (pinfunction "OUT_14") (pintype "output"))
      (node (ref "R68") (pin "2") (pinfunction "2_2") (pintype "passive"))
      (node (ref "TEENSY_LC") (pin "A11") (pinfunction "A11_A11") (pintype "bidirectional"))
    )
    (net (code "22") (name "/AREF") (class "Default")
      (node (ref "TEENSY_LC") (pin "AREF") (pinfunction "AREF_AREF") (pintype "power_in"))
    )
    (net (code "23") (name "/VUSB") (class "Default")
      (node (ref "TEENSY_LC") (pin "VUSB") (pinfunction "VUSB_VUSB") (pintype "power_in"))
    )
    (net (code "24") (name "5V") (class "Default")
      (node (ref "5V") (pin "1") (pinfunction "3_1") (pintype "passive"))
      (node (ref "5V1") (pin "1") (pinfunction "3_1") (pintype "passive"))
      (node (ref "C3") (pin "+") (pinfunction "+_+") (pintype "passive"))
      (node (ref "IC1") (pin "10") (pinfunction "SCL_10") (pintype "input"))
      (node (ref "IC1") (pin "16") (pinfunction "VCC_16") (pintype "power_in"))
      (node (ref "IC2") (pin "3") (pinfunction "VO_3") (pintype "passive"))
      (node (ref "TEENSY_LC") (pin "VIN") (pinfunction "VIN_VIN") (pintype "power_in"))
    )
    (net (code "25") (name "GND") (class "Default")
      (node (ref "C1") (pin "-") (pinfunction "-_-") (pintype "passive"))
      (node (ref "C15") (pin "1") (pinfunction "1_1") (pintype "passive"))
      (node (ref "C18") (pin "1") (pinfunction "1_1") (pintype "passive"))
      (node (ref "C2") (pin "+") (pinfunction "+_+") (pintype "passive"))
      (node (ref "C26") (pin "1") (pinfunction "1_1") (pintype "passive"))
      (node (ref "C29") (pin "+") (pinfunction "+_+") (pintype "passive"))
      (node (ref "C3") (pin "-") (pinfunction "-_-") (pintype "passive"))
      (node (ref "C6") (pin "1") (pinfunction "1_1") (pintype "passive"))
      (node (ref "GND") (pin "1") (pinfunction "3_1") (pintype "passive"))
      (node (ref "GND1") (pin "1") (pinfunction "3_1") (pintype "passive"))
      (node (ref "GND2") (pin "1") (pinfunction "3_1") (pintype "passive"))
      (node (ref "GND3") (pin "1") (pinfunction "3_1") (pintype "passive"))
      (node (ref "IC1") (pin "13") (pinfunction "G_13") (pintype "input"))
      (node (ref "IC1") (pin "8") (pinfunction "GND_8") (pintype "power_in"))
      (node (ref "IC2") (pin "2") (pinfunction "GND_2") (pintype "passive"))
      (node (ref "IC3") (pin "10") (pinfunction "+IN_10") (pintype "input"))
      (node (ref "IC3") (pin "11") (pinfunction "V-_11") (pintype "power_in"))
      (node (ref "IC3") (pin "12") (pinfunction "+IN_12") (pintype "input"))
      (node (ref "IC3") (pin "3") (pinfunction "+IN_3") (pintype "input"))
      (node (ref "IC3") (pin "5") (pinfunction "+IN_5") (pintype "input"))
      (node (ref "IC4") (pin "10") (pinfunction "+IN_10") (pintype "input"))
      (node (ref "IC4") (pin "11") (pinfunction "V-_11") (pintype "power_in"))
      (node (ref "IC4") (pin "12") (pinfunction "+IN_12") (pintype "input"))
      (node (ref "IC4") (pin "3") (pinfunction "+IN_3") (pintype "input"))
      (node (ref "IC4") (pin "5") (pinfunction "+IN_5") (pintype "input"))
      (node (ref "IC5") (pin "10") (pinfunction "+IN_10") (pintype "input"))
      (node (ref "IC5") (pin "11") (pinfunction "V-_11") (pintype "power_in"))
      (node (ref "IC5") (pin "12") (pinfunction "+IN_12") (pintype "input"))
      (node (ref "IC5") (pin "3") (pinfunction "+IN_3") (pintype "input"))
      (node (ref "IC5") (pin "5") (pinfunction "+IN_5") (pintype "input"))
      (node (ref "IC7") (pin "1") (pinfunction "GND_1") (pintype "passive"))
      (node (ref "IC8") (pin "2") (pinfunction "C_2") (pintype "input"))
      (node (ref "Q1") (pin "3") (pinfunction "E_3") (pintype "passive"))
      (node (ref "Q2") (pin "3") (pinfunction "E_3") (pintype "passive"))
      (node (ref "R56") (pin "1") (pinfunction "1_1") (pintype "passive"))
      (node (ref "R60") (pin "1") (pinfunction "1_1") (pintype "passive"))
      (node (ref "TEENSY_LC") (pin "AGND") (pinfunction "GND_AGND") (pintype "power_in"))
      (node (ref "TEENSY_LC") (pin "GND") (pinfunction "GND_GND") (pintype "power_in"))
    )
    (net (code "26") (name "Net-(0_RX-3)") (class "Default")
      (node (ref "0_RX") (pin "1") (pinfunction "3_1") (pintype "passive"))
      (node (ref "TEENSY_LC") (pin "0") (pinfunction "0/RX1/T/MOSI1_0") (pintype "bidirectional"))
    )
    (net (code "27") (name "Net-(1_TX-3)") (class "Default")
      (node (ref "1_TX") (pin "1") (pinfunction "3_1") (pintype "passive"))
      (node (ref "TEENSY_LC") (pin "1") (pinfunction "1/TX1/T/MISO1_1") (pintype "bidirectional"))
    )
    (net (code "28") (name "Net-(10_CS-3)") (class "Default")
      (node (ref "10_CS") (pin "1") (pinfunction "3_1") (pintype "passive"))
      (node (ref "TEENSY_LC") (pin "10") (pinfunction "10/TX2/PWM_10") (pintype "bidirectional"))
    )
    (net (code "29") (name "Net-(11_MOSI-3)") (class "Default")
      (node (ref "11_MOSI") (pin "1") (pinfunction "3_1") (pintype "passive"))
      (node (ref "TEENSY_LC") (pin "11") (pinfunction "11/MOSI_11") (pintype "bidirectional"))
    )
    (net (code "30") (name "Net-(12_MISO-3)") (class "Default")
      (node (ref "12_MISO") (pin "1") (pinfunction "3_1") (pintype "passive"))
      (node (ref "TEENSY_LC") (pin "12") (pinfunction "12/MISO_12") (pintype "bidirectional"))
    )
    (net (code "31") (name "Net-(13_SCK-3)") (class "Default")
      (node (ref "13_SCK") (pin "1") (pinfunction "3_1") (pintype "passive"))
      (node (ref "TEENSY_LC") (pin "13") (pinfunction "13/SCK/LED_13") (pintype "bidirectional"))
    )
    (net (code "32") (name "Net-(CLKIN-3)") (class "Default")
      (node (ref "CLKIN") (pin "1") (pinfunction "3_1") (pintype "passive"))
      (node (ref "R55") (pin "1") (pinfunction "1_1") (pintype "passive"))
    )
    (net (code "33") (name "Net-(CV1A-3)") (class "Default")
      (node (ref "CV1A") (pin "1") (pinfunction "3_1") (pintype "passive"))
      (node (ref "R22") (pin "1") (pinfunction "1_1") (pintype "passive"))
    )
    (net (code "34") (name "Net-(CV1B-3)") (class "Default")
      (node (ref "CV1B") (pin "1") (pinfunction "3_1") (pintype "passive"))
      (node (ref "R23") (pin "1") (pinfunction "1_1") (pintype "passive"))
    )
    (net (code "35") (name "Net-(CV2A-3)") (class "Default")
      (node (ref "CV2A") (pin "1") (pinfunction "3_1") (pintype "passive"))
      (node (ref "R27") (pin "1") (pinfunction "1_1") (pintype "passive"))
    )
    (net (code "36") (name "Net-(CV2B-3)") (class "Default")
      (node (ref "CV2B") (pin "1") (pinfunction "3_1") (pintype "passive"))
      (node (ref "R28") (pin "1") (pinfunction "1_1") (pintype "passive"))
    )
    (net (code "37") (name "Net-(CV3A-3)") (class "Default")
      (node (ref "CV3A") (pin "1") (pinfunction "3_1") (pintype "passive"))
      (node (ref "R31") (pin "1") (pinfunction "1_1") (pintype "passive"))
    )
    (net (code "38") (name "Net-(CV3B-3)") (class "Default")
      (node (ref "CV3B") (pin "1") (pinfunction "3_1") (pintype "passive"))
      (node (ref "R32") (pin "1") (pinfunction "1_1") (pintype "passive"))
    )
    (net (code "39") (name "Net-(CV4A-3)") (class "Default")
      (node (ref "CV4A") (pin "1") (pinfunction "3_1") (pintype "passive"))
      (node (ref "R35") (pin "1") (pinfunction "1_1") (pintype "passive"))
    )
    (net (code "40") (name "Net-(CV4B-3)") (class "Default")
      (node (ref "CV4B") (pin "1") (pinfunction "3_1") (pintype "passive"))
      (node (ref "R36") (pin "1") (pinfunction "1_1") (pintype "passive"))
    )
    (net (code "41") (name "Net-(CV5A-3)") (class "Default")
      (node (ref "CV5A") (pin "1") (pinfunction "3_1") (pintype "passive"))
      (node (ref "R39") (pin "1") (pinfunction "1_1") (pintype "passive"))
    )
    (net (code "42") (name "Net-(CV5B-3)") (class "Default")
      (node (ref "CV5B") (pin "1") (pinfunction "3_1") (pintype "passive"))
      (node (ref "R40") (pin "1") (pinfunction "1_1") (pintype "passive"))
    )
    (net (code "43") (name "Net-(CV6A-3)") (class "Default")
      (node (ref "CV6A") (pin "1") (pinfunction "3_1") (pintype "passive"))
      (node (ref "R44") (pin "1") (pinfunction "1_1") (pintype "passive"))
    )
    (net (code "44") (name "Net-(CV6B-3)") (class "Default")
      (node (ref "CV6B") (pin "1") (pinfunction "3_1") (pintype "passive"))
      (node (ref "R45") (pin "1") (pinfunction "1_1") (pintype "passive"))
    )
    (net (code "45") (name "Net-(CV7A-3)") (class "Default")
      (node (ref "CV7A") (pin "1") (pinfunction "3_1") (pintype "passive"))
      (node (ref "R47") (pin "1") (pinfunction "1_1") (pintype "passive"))
    )
    (net (code "46") (name "Net-(CV7B-3)") (class "Default")
      (node (ref "CV7B") (pin "1") (pinfunction "3_1") (pintype "passive"))
      (node (ref "R48") (pin "1") (pinfunction "1_1") (pintype "passive"))
    )
    (net (code "47") (name "Net-(CV8A-3)") (class "Default")
      (node (ref "CV8A") (pin "1") (pinfunction "3_1") (pintype "passive"))
      (node (ref "R51") (pin "1") (pinfunction "1_1") (pintype "passive"))
    )
    (net (code "48") (name "Net-(CV8B-3)") (class "Default")
      (node (ref "CV8B") (pin "1") (pinfunction "3_1") (pintype "passive"))
      (node (ref "R52") (pin "1") (pinfunction "1_1") (pintype "passive"))
    )
    (net (code "49") (name "Net-(CV9A-3)") (class "Default")
      (node (ref "CV9A") (pin "1") (pinfunction "3_1") (pintype "passive"))
      (node (ref "R11") (pin "1") (pinfunction "1_1") (pintype "passive"))
    )
    (net (code "50") (name "Net-(CV9B-3)") (class "Default")
      (node (ref "CV9B") (pin "1") (pinfunction "3_1") (pintype "passive"))
      (node (ref "R12") (pin "1") (pinfunction "1_1") (pintype "passive"))
    )
    (net (code "51") (name "Net-(CV10A-3)") (class "Default")
      (node (ref "CV10A") (pin "1") (pinfunction "3_1") (pintype "passive"))
      (node (ref "R62") (pin "1") (pinfunction "1_1") (pintype "passive"))
    )
    (net (code "52") (name "Net-(CV10B-3)") (class "Default")
      (node (ref "CV10B") (pin "1") (pinfunction "3_1") (pintype "passive"))
      (node (ref "R63") (pin "1") (pinfunction "1_1") (pintype "passive"))
    )
    (net (code "53") (name "Net-(CV11A-3)") (class "Default")
      (node (ref "CV11A") (pin "1") (pinfunction "3_1") (pintype "passive"))
      (node (ref "R65") (pin "1") (pinfunction "1_1") (pintype "passive"))
    )
    (net (code "54") (name "Net-(CV11B-3)") (class "Default")
      (node (ref "CV11B") (pin "1") (pinfunction "3_1") (pintype "passive"))
      (node (ref "R66") (pin "1") (pinfunction "1_1") (pintype "passive"))
    )
    (net (code "55") (name "Net-(CV12A-3)") (class "Default")
      (node (ref "CV12A") (pin "1") (pinfunction "3_1") (pintype "passive"))
      (node (ref "R69") (pin "1") (pinfunction "1_1") (pintype "passive"))
    )
    (net (code "56") (name "Net-(CV12B-3)") (class "Default")
      (node (ref "CV12B") (pin "1") (pinfunction "3_1") (pintype "passive"))
      (node (ref "R70") (pin "1") (pinfunction "1_1") (pintype "passive"))
    )
    (net (code "57") (name "Net-(ENC1-3)") (class "Default")
      (node (ref "ENC1") (pin "1") (pinfunction "3_1") (pintype "passive"))
      (node (ref "TEENSY_LC") (pin "7") (pinfunction "7/RX3_7") (pintype "bidirectional"))
    )
    (net (code "58") (name "Net-(ENC2-3)") (class "Default")
      (node (ref "ENC2") (pin "1") (pinfunction "3_1") (pintype "passive"))
      (node (ref "TEENSY_LC") (pin "8") (pinfunction "8/TX3_8") (pintype "bidirectional"))
    )
    (net (code "59") (name "Net-(ENCBTN-3)") (class "Default")
      (node (ref "ENCBTN") (pin "1") (pinfunction "3_1") (pintype "passive"))
      (node (ref "TEENSY_LC") (pin "9") (pinfunction "9/RX2/PWM_9") (pintype "bidirectional"))
    )
    (net (code "60") (name "Net-(IC1A-QA)") (class "Default")
      (node (ref "IC1") (pin "15") (pinfunction "QA_15") (pintype "tri_state"))
      (node (ref "R1") (pin "1") (pinfunction "1_1") (pintype "passive"))
    )
    (net (code "61") (name "Net-(IC1A-QB)") (class "Default")
      (node (ref "IC1") (pin "1") (pinfunction "QB_1") (pintype "tri_state"))
      (node (ref "R2") (pin "1") (pinfunction "1_1") (pintype "passive"))
    )
    (net (code "62") (name "Net-(IC1A-QC)") (class "Default")
      (node (ref "IC1") (pin "2") (pinfunction "QC_2") (pintype "tri_state"))
      (node (ref "R3") (pin "1") (pinfunction "1_1") (pintype "passive"))
    )
    (net (code "63") (name "Net-(IC1A-QD)") (class "Default")
      (node (ref "IC1") (pin "3") (pinfunction "QD_3") (pintype "tri_state"))
      (node (ref "R4") (pin "1") (pinfunction "1_1") (pintype "passive"))
    )
    (net (code "64") (name "Net-(IC1A-QE)") (class "Default")
      (node (ref "IC1") (pin "4") (pinfunction "QE_4") (pintype "tri_state"))
      (node (ref "R5") (pin "1") (pinfunction "1_1") (pintype "passive"))
    )
    (net (code "65") (name "Net-(IC1A-QF)") (class "Default")
      (node (ref "IC1") (pin "5") (pinfunction "QF_5") (pintype "tri_state"))
      (node (ref "R6") (pin "1") (pinfunction "1_1") (pintype "passive"))
    )
    (net (code "66") (name "Net-(IC1A-QG)") (class "Default")
      (node (ref "IC1") (pin "6") (pinfunction "QG_6") (pintype "tri_state"))
      (node (ref "R9") (pin "1") (pinfunction "1_1") (pintype "passive"))
    )
    (net (code "67") (name "Net-(IC1A-QH)") (class "Default")
      (node (ref "IC1") (pin "7") (pinfunction "QH_7") (pintype "tri_state"))
      (node (ref "R10") (pin "1") (pinfunction "1_1") (pintype "passive"))
    )
    (net (code "68") (name "Net-(IC3A--IN)") (class "Default")
      (node (ref "C7") (pin "1") (pinfunction "1_1") (pintype "passive"))
      (node (ref "IC3") (pin "2") (pinfunction "-IN_2") (pintype "input"))
      (node (ref "R11") (pin "2") (pinfunction "2_2") (pintype "passive"))
      (node (ref "R12") (pin "2") (pinfunction "2_2") (pintype "passive"))
      (node (ref "R13") (pin "2") (pinfunction "2_2") (pintype "passive"))
      (node (ref "R8") (pin "1") (pinfunction "1_1") (pintype "passive"))
    )
    (net (code "69") (name "Net-(IC3B--IN)") (class "Default")
      (node (ref "C10") (pin "1") (pinfunction "1_1") (pintype "passive"))
      (node (ref "IC3") (pin "6") (pinfunction "-IN_6") (pintype "input"))
      (node (ref "R15") (pin "1") (pinfunction "1_1") (pintype "passive"))
      (node (ref "R29") (pin "2") (pinfunction "2_2") (pintype "passive"))
      (node (ref "R62") (pin "2") (pinfunction "2_2") (pintype "passive"))
      (node (ref "R63") (pin "2") (pinfunction "2_2") (pintype "passive"))
    )
    (net (code "70") (name "Net-(IC3C--IN)") (class "Default")
      (node (ref "C11") (pin "1") (pinfunction "1_1") (pintype "passive"))
      (node (ref "IC3") (pin "9") (pinfunction "-IN_9") (pintype "input"))
      (node (ref "R64") (pin "1") (pinfunction "1_1") (pintype "passive"))
      (node (ref "R65") (pin "2") (pinfunction "2_2") (pintype "passive"))
      (node (ref "R66") (pin "2") (pinfunction "2_2") (pintype "passive"))
      (node (ref "R67") (pin "2") (pinfunction "2_2") (pintype "passive"))
    )
    (net (code "71") (name "Net-(IC3D--IN)") (class "Default")
      (node (ref "C14") (pin "1") (pinfunction "1_1") (pintype "passive"))
      (node (ref "IC3") (pin "13") (pinfunction "-IN_13") (pintype "input"))
      (node (ref "R68") (pin "1") (pinfunction "1_1") (pintype "passive"))
      (node (ref "R69") (pin "2") (pinfunction "2_2") (pintype "passive"))
      (node (ref "R70") (pin "2") (pinfunction "2_2") (pintype "passive"))
      (node (ref "R71") (pin "2") (pinfunction "2_2") (pintype "passive"))
    )
    (net (code "72") (name "Net-(IC4A--IN)") (class "Default")
      (node (ref "C16") (pin "1") (pinfunction "1_1") (pintype "passive"))
      (node (ref "IC4") (pin "2") (pinfunction "-IN_2") (pintype "input"))
      (node (ref "R21") (pin "1") (pinfunction "1_1") (pintype "passive"))
      (node (ref "R22") (pin "2") (pinfunction "2_2") (pintype "passive"))
      (node (ref "R23") (pin "2") (pinfunction "2_2") (pintype "passive"))
      (node (ref "R24") (pin "2") (pinfunction "2_2") (pintype "passive"))
    )
    (net (code "73") (name "Net-(IC4B--IN)") (class "Default")
      (node (ref "C17") (pin "1") (pinfunction "1_1") (pintype "passive"))
      (node (ref "IC4") (pin "6") (pinfunction "-IN_6") (pintype "input"))
      (node (ref "R25") (pin "1") (pinfunction "1_1") (pintype "passive"))
      (node (ref "R26") (pin "2") (pinfunction "2_2") (pintype "passive"))
      (node (ref "R27") (pin "2") (pinfunction "2_2") (pintype "passive"))
      (node (ref "R28") (pin "2") (pinfunction "2_2") (pintype "passive"))
    )
    (net (code "74") (name "Net-(IC4C--IN)") (class "Default")
      (node (ref "C20") (pin "1") (pinfunction "1_1") (pintype "passive"))
      (node (ref "IC4") (pin "9") (pinfunction "-IN_9") (pintype "input"))
      (node (ref "R30") (pin "1") (pinfunction "1_1") (pintype "passive"))
      (node (ref "R31") (pin "2") (pinfunction "2_2") (pintype "passive"))
      (node (ref "R32") (pin "2") (pinfunction "2_2") (pintype "passive"))
      (node (ref "R33") (pin "2") (pinfunction "2_2") (pintype "passive"))
    )
    (net (code "75") (name "Net-(IC4D--IN)") (class "Default")
      (node (ref "C21") (pin "1") (pinfunction "1_1") (pintype "passive"))
      (node (ref "IC4") (pin "13") (pinfunction "-IN_13") (pintype "input"))
      (node (ref "R34") (pin "1") (pinfunction "1_1") (pintype "passive"))
      (node (ref "R35") (pin "2") (pinfunction "2_2") (pintype "passive"))
      (node (ref "R36") (pin "2") (pinfunction "2_2") (pintype "passive"))
      (node (ref "R37") (pin "2") (pinfunction "2_2") (pintype "passive"))
    )
    (net (code "76") (name "Net-(IC5A--IN)") (class "Default")
      (node (ref "C22") (pin "1") (pinfunction "1_1") (pintype "passive"))
      (node (ref "IC5") (pin "2") (pinfunction "-IN_2") (pintype "input"))
      (node (ref "R38") (pin "1") (pinfunction "1_1") (pintype "passive"))
      (node (ref "R39") (pin "2") (pinfunction "2_2") (pintype "passive"))
      (node (ref "R40") (pin "2") (pinfunction "2_2") (pintype "passive"))
      (node (ref "R41") (pin "2") (pinfunction "2_2") (pintype "passive"))
    )
    (net (code "77") (name "Net-(IC5B--IN)") (class "Default")
      (node (ref "C23") (pin "1") (pinfunction "1_1") (pintype "passive"))
      (node (ref "IC5") (pin "6") (pinfunction "-IN_6") (pintype "input"))
      (node (ref "R42") (pin "1") (pinfunction "1_1") (pintype "passive"))
      (node (ref "R43") (pin "2") (pinfunction "2_2") (pintype "passive"))
      (node (ref "R44") (pin "2") (pinfunction "2_2") (pintype "passive"))
      (node (ref "R45") (pin "2") (pinfunction "2_2") (pintype "passive"))
    )
    (net (code "78") (name "Net-(IC5C--IN)") (class "Default")
      (node (ref "C24") (pin "1") (pinfunction "1_1") (pintype "passive"))
      (node (ref "IC5") (pin "9") (pinfunction "-IN_9") (pintype "input"))
      (node (ref "R46") (pin "1") (pinfunction "1_1") (pintype "passive"))
      (node (ref "R47") (pin "2") (pinfunction "2_2") (pintype "passive"))
      (node (ref "R48") (pin "2") (pinfunction "2_2") (pintype "passive"))
      (node (ref "R49") (pin "2") (pinfunction "2_2") (pintype "passive"))
    )
    (net (code "79") (name "Net-(IC5D--IN)") (class "Default")
      (node (ref "C25") (pin "1") (pinfunction "1_1") (pintype "passive"))
      (node (ref "IC5") (pin "13") (pinfunction "-IN_13") (pintype "input"))
      (node (ref "R50") (pin "1") (pinfunction "1_1") (pintype "passive"))
      (node (ref "R51") (pin "2") (pinfunction "2_2") (pintype "passive"))
      (node (ref "R52") (pin "2") (pinfunction "2_2") (pintype "passive"))
      (node (ref "R53") (pin "2") (pinfunction "2_2") (pintype "passive"))
    )
    (net (code "80") (name "Net-(OUT1A-3)") (class "Default")
      (node (ref "OUT1A") (pin "1") (pinfunction "3_1") (pintype "passive"))
      (node (ref "OUT1A1") (pin "1") (pinfunction "3_1") (pintype "passive"))
      (node (ref "R1") (pin "2") (pinfunction "2_2") (pintype "passive"))
    )
    (net (code "81") (name "Net-(OUT2A-3)") (class "Default")
      (node (ref "OUT2A") (pin "1") (pinfunction "3_1") (pintype "passive"))
      (node (ref "OUT2A1") (pin "1") (pinfunction "3_1") (pintype "passive"))
      (node (ref "R2") (pin "2") (pinfunction "2_2") (pintype "passive"))
    )
    (net (code "82") (name "Net-(OUT3A-3)") (class "Default")
      (node (ref "OUT3A") (pin "1") (pinfunction "3_1") (pintype "passive"))
      (node (ref "OUT3A1") (pin "1") (pinfunction "3_1") (pintype "passive"))
      (node (ref "R3") (pin "2") (pinfunction "2_2") (pintype "passive"))
    )
    (net (code "83") (name "Net-(OUT4A-3)") (class "Default")
      (node (ref "OUT4A") (pin "1") (pinfunction "3_1") (pintype "passive"))
      (node (ref "OUT4A1") (pin "1") (pinfunction "3_1") (pintype "passive"))
      (node (ref "R4") (pin "2") (pinfunction "2_2") (pintype "passive"))
    )
    (net (code "84") (name "Net-(OUT5A-3)") (class "Default")
      (node (ref "OUT5A") (pin "1") (pinfunction "3_1") (pintype "passive"))
      (node (ref "OUT5A1") (pin "1") (pinfunction "3_1") (pintype "passive"))
      (node (ref "R5") (pin "2") (pinfunction "2_2") (pintype "passive"))
    )
    (net (code "85") (name "Net-(OUT6A-3)") (class "Default")
      (node (ref "OUT6A") (pin "1") (pinfunction "3_1") (pintype "passive"))
      (node (ref "OUT6A1") (pin "1") (pinfunction "3_1") (pintype "passive"))
      (node (ref "R6") (pin "2") (pinfunction "2_2") (pintype "passive"))
    )
    (net (code "86") (name "Net-(OUT7A-3)") (class "Default")
      (node (ref "OUT7A") (pin "1") (pinfunction "3_1") (pintype "passive"))
      (node (ref "OUT7A1") (pin "1") (pinfunction "3_1") (pintype "passive"))
      (node (ref "R9") (pin "2") (pinfunction "2_2") (pintype "passive"))
    )
    (net (code "87") (name "Net-(OUT8A-3)") (class "Default")
      (node (ref "OUT8A") (pin "1") (pinfunction "3_1") (pintype "passive"))
      (node (ref "OUT8A1") (pin "1") (pinfunction "3_1") (pintype "passive"))
      (node (ref "R10") (pin "2") (pinfunction "2_2") (pintype "passive"))
    )
    (net (code "88") (name "Net-(Q1-B)") (class "Default")
      (node (ref "Q1") (pin "2") (pinfunction "B_2") (pintype "passive"))
      (node (ref "R55") (pin "2") (pinfunction "2_2") (pintype "passive"))
      (node (ref "R56") (pin "2") (pinfunction "2_2") (pintype "passive"))
    )
    (net (code "89") (name "Net-(Q1-C)") (class "Default")
      (node (ref "Q1") (pin "1") (pinfunction "C_1") (pintype "passive"))
      (node (ref "R54") (pin "1") (pinfunction "1_1") (pintype "passive"))
      (node (ref "R57") (pin "1") (pinfunction "1_1") (pintype "passive"))
    )
    (net (code "90") (name "Net-(Q2-B)") (class "Default")
      (node (ref "Q2") (pin "2") (pinfunction "B_2") (pintype "passive"))
      (node (ref "R59") (pin "2") (pinfunction "2_2") (pintype "passive"))
      (node (ref "R60") (pin "2") (pinfunction "2_2") (pintype "passive"))
    )
    (net (code "91") (name "Net-(Q2-C)") (class "Default")
      (node (ref "Q2") (pin "1") (pinfunction "C_1") (pintype "passive"))
      (node (ref "R58") (pin "1") (pinfunction "1_1") (pintype "passive"))
      (node (ref "R61") (pin "1") (pinfunction "1_1") (pintype "passive"))
    )
    (net (code "92") (name "Net-(RSTIN-3)") (class "Default")
      (node (ref "R59") (pin "1") (pinfunction "1_1") (pintype "passive"))
      (node (ref "RSTIN") (pin "1") (pinfunction "3_1") (pintype "passive"))
    )
    (net (code "93") (name "unconnected-(IC1A-QH*-Pad9)") (class "Default")
      (node (ref "IC1") (pin "9") (pinfunction "QH*_9") (pintype "tri_state"))
    )
  )
)
